# MCU.net
KiCad netlist of a schematic drawn in Altium Designer
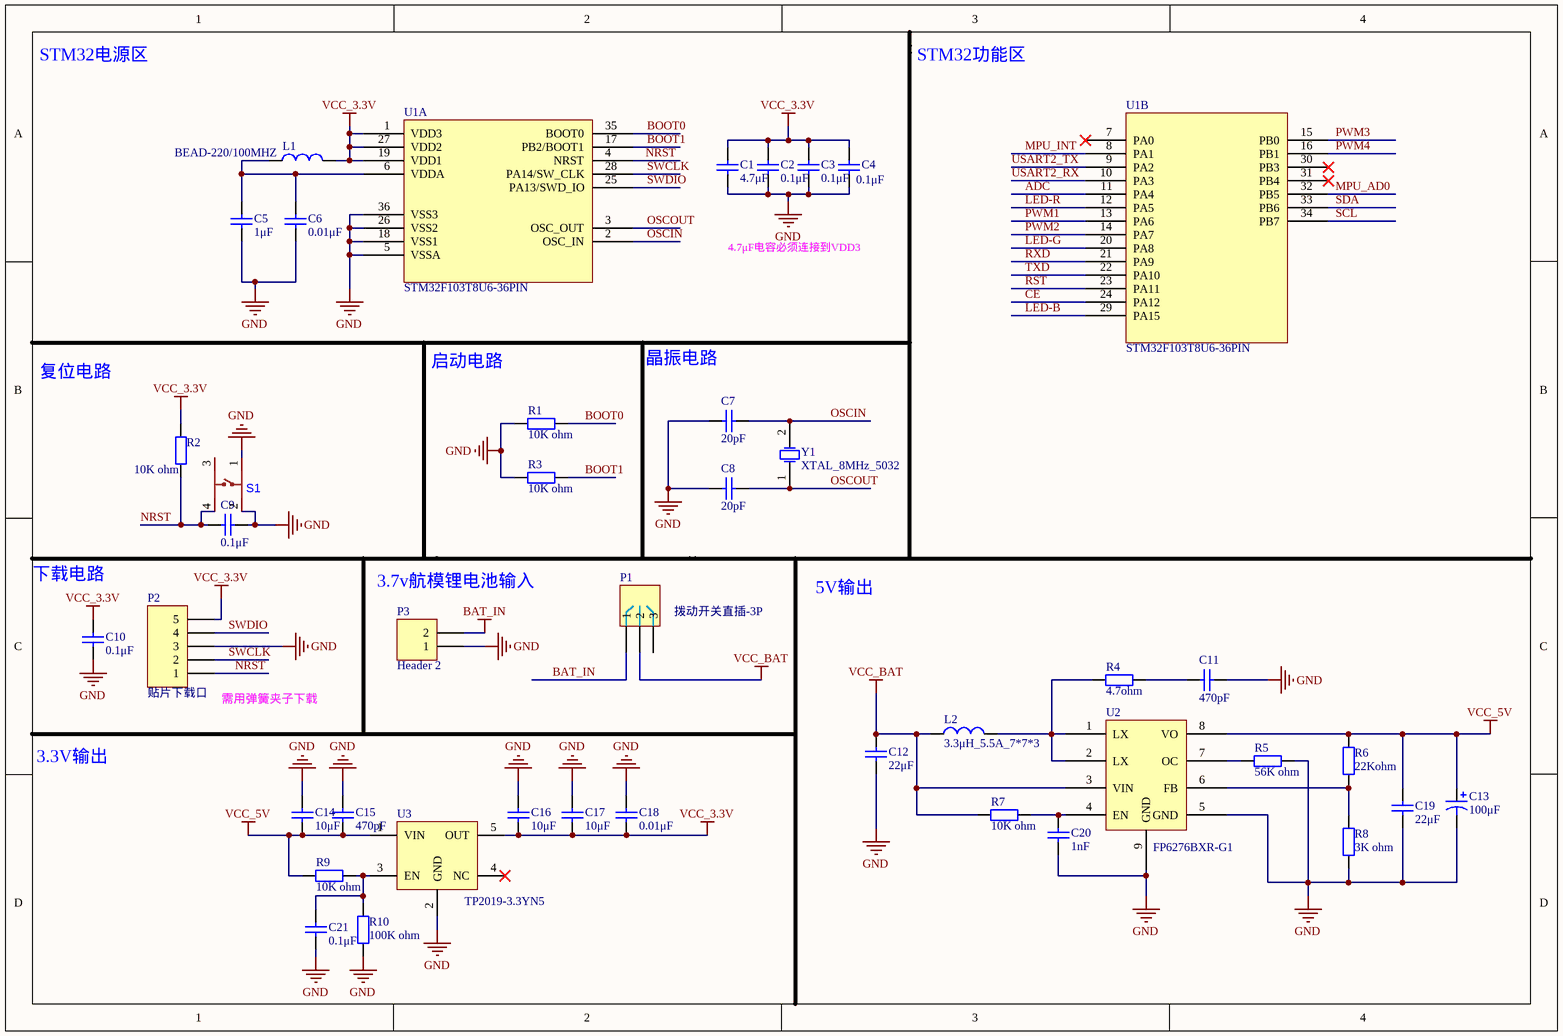
[diagram p0: MCU.SchDoc]

(export (version "E")
  (design (tool "Eeschema 10.0.6"))
  (components
    (comp (ref "C1")
      (value "4.7μF")
      (footprint "0603C")
      (description "0.1μF_50V,X7R,±5%")
      (libsource (lib "Smart-Plane_1") (part "Cap_0.1μF_50V_0603"))
    )
    (comp (ref "C2")
      (value "0.1μF")
      (footprint "0603C")
      (description "0.1μF_50V,X7R,±5%")
      (libsource (lib "Smart-Plane_1") (part "Cap_0.1μF_50V_0603"))
    )
    (comp (ref "C3")
      (value "0.1μF")
      (footprint "0603C")
      (description "0.1μF_50V,X7R,±5%")
      (libsource (lib "Smart-Plane_1") (part "Cap_0.1μF_50V_0603"))
    )
    (comp (ref "C4")
      (value "0.1μF")
      (footprint "0603C")
      (description "0.1μF_50V,X7R,±5%")
      (libsource (lib "Smart-Plane_1") (part "Cap_0.1μF_50V_0603"))
    )
    (comp (ref "C5")
      (value "1μF")
      (footprint "0603C")
      (description "0.1μF_50V,X7R,±5%")
      (libsource (lib "Smart-Plane_1") (part "Cap_0.1μF_50V_0603"))
    )
    (comp (ref "C6")
      (value "0.01μF")
      (footprint "0603C")
      (description "0.1μF_50V,X7R,±5%")
      (libsource (lib "Smart-Plane_1") (part "Cap_0.1μF_50V_0603"))
    )
    (comp (ref "C7")
      (value "20pF")
      (footprint "0603C")
      (description "20pF_50V,CH,±5%")
      (libsource (lib "Yang_Lib") (part "Cap_20pF_50V_0603"))
    )
    (comp (ref "C8")
      (value "20pF")
      (footprint "0603C")
      (description "20pF_50V,CH,±5%")
      (libsource (lib "Yang_Lib") (part "Cap_20pF_50V_0603"))
    )
    (comp (ref "C9")
      (value "0.1μF")
      (footprint "0603C")
      (description "0.1μF_50V,X7R,±5%")
      (libsource (lib "Smart-Plane_1") (part "Cap_0.1μF_50V_0603"))
    )
    (comp (ref "C10")
      (value "0.1μF")
      (footprint "0603C")
      (description "0.1μF_50V,X7R,±5%")
      (libsource (lib "Smart-Plane_1") (part "Cap_0.1μF_50V_0603"))
    )
    (comp (ref "C11")
      (value "470pF")
      (footprint "0603C")
      (description "2.2nF_50V,X7R,10%")
      (libsource (lib "Yang_Lib") (part "Cap_2.2nF_50V_0603"))
    )
    (comp (ref "C12")
      (value "22μF")
      (footprint "1206C")
      (description "22μF_35V,20%")
      (libsource (lib "Yang_Lib") (part "Cap_22μF_35V_1206"))
    )
    (comp (ref "C13")
      (value "100μF")
      (footprint "D7343C")
      (description "100μF_16V")
      (libsource (lib "Yang_Lib") (part "Cap_100μF_16V_D7343"))
    )
    (comp (ref "C14")
      (value "10μF")
      (footprint "0603C")
      (description "1μF_50V,X5R,±10%")
      (libsource (lib "Yang_Lib") (part "Cap_1μF_50V_0603"))
    )
    (comp (ref "C15")
      (value "470pF")
      (footprint "0603C")
      (description "1μF_50V,X5R,±10%")
      (libsource (lib "Yang_Lib") (part "Cap_1μF_50V_0603"))
    )
    (comp (ref "C16")
      (value "10μF")
      (footprint "0603C")
      (description "1μF_50V,X5R,±10%")
      (libsource (lib "Yang_Lib") (part "Cap_1μF_50V_0603"))
    )
    (comp (ref "C17")
      (value "10μF")
      (footprint "0603C")
      (description "10μF_35V,X5R,20%")
      (libsource (lib "Yang_Lib") (part "Cap_10μF_35V_0603"))
    )
    (comp (ref "C18")
      (value "0.01μF")
      (footprint "0603C")
      (description "0.1μF_50V,X7R,±5%")
      (libsource (lib "Smart-Plane_1") (part "Cap_0.1μF_50V_0603"))
    )
    (comp (ref "C19")
      (value "22μF")
      (footprint "1206C")
      (description "22μF_35V,20%")
      (libsource (lib "Yang_Lib") (part "Cap_22μF_35V_1206"))
    )
    (comp (ref "C20")
      (value "1nF")
      (footprint "0603C")
      (description "1μF_50V,X5R,±10%")
      (libsource (lib "Yang_Lib") (part "Cap_1μF_50V_0603"))
    )
    (comp (ref "C21")
      (value "0.1μF")
      (footprint "0603C")
      (description "1μF_50V,X5R,±10%")
      (libsource (lib "Yang_Lib") (part "Cap_1μF_50V_0603"))
    )
    (comp (ref "L1")
      (value "BEAD-220/100MHZ")
      (footprint "0603R")
      (libsource (lib "Yang_Lib") (part "BEAD-220/100MHZ_0603"))
    )
    (comp (ref "L2")
      (value "3.3μH_5.5A_7*7*3")
      (footprint "7*7*3mm - 06030")
      (description "4.7μH_5.5A_")
      (libsource (lib "Yang_Lib") (part "4.7μH_5.5A_7*7*3"))
    )
    (comp (ref "P1")
      (value "拨动开关直插-3P")
      (footprint "Switch-3P")
      (libsource (lib "Smart-Telecontrol") (part "拨动开关直插-3P"))
    )
    (comp (ref "P2")
      (value "贴片下载口")
      (footprint "download")
      (description "微型下载口")
      (libsource (lib "Smart-Plane_1") (part "微型下载口"))
    )
    (comp (ref "P3")
      (value "Header 2")
      (footprint "HDR1X2")
      (description "Header, 2-Pin")
      (fields (field (name "PUBLISHER") "Altium Limited"))
      (libsource (lib "Miscellaneous Connectors") (part "Header 2"))
    )
    (comp (ref "R1")
      (value "10K ohm")
      (footprint "0603R")
      (description "10K ohm,1%")
      (libsource (lib "") (part "Res_10K ohm_0603_1"))
    )
    (comp (ref "R2")
      (value "10K ohm")
      (footprint "0603R")
      (description "10K ohm,1%")
      (libsource (lib "Smart-Plane_1") (part "Res_10K ohm_0603"))
    )
    (comp (ref "R3")
      (value "10K ohm")
      (footprint "0603R")
      (description "10K ohm,1%")
      (libsource (lib "") (part "Res_10K ohm_0603_1"))
    )
    (comp (ref "R4")
      (value "4.7ohm")
      (footprint "0603R")
      (description "24K ohm,1%")
      (libsource (lib "Yang_Lib") (part "Res_24K ohm_0603"))
    )
    (comp (ref "R5")
      (value "56K ohm")
      (footprint "0603R")
      (description "30K ohm,1%")
      (libsource (lib "Yang_Lib") (part "Res_30K ohm_0603"))
    )
    (comp (ref "R6")
      (value "22Kohm")
      (footprint "0603R")
      (description "100K ohm_5%")
      (libsource (lib "Smart-Plane_1") (part "Res_100Kohm_0603"))
    )
    (comp (ref "R7")
      (value "10K ohm")
      (footprint "0603R")
      (description "10K ohm,1%")
      (libsource (lib "") (part "Res_10K ohm_0603_1"))
    )
    (comp (ref "R8")
      (value "3K ohm")
      (footprint "0603R")
      (description "13K ohm,1%")
      (libsource (lib "Smart-Plane_1") (part "Res_13K ohm_0603"))
    )
    (comp (ref "R9")
      (value "10K ohm")
      (footprint "0603R")
      (description "10K ohm,1%")
      (libsource (lib "") (part "Res_10K ohm_0603_1"))
    )
    (comp (ref "R10")
      (value "100K ohm")
      (footprint "0603R")
      (description "10K ohm,1%")
      (libsource (lib "") (part "Res_10K ohm_0603_2"))
    )
    (comp (ref "S1")
      (value "BX-TS-26-4416TT")
      (footprint "SW-SMD_4P-L5.2-W5.2-P3.70-LS6.5")
      (fields (field (name "MANUFACTURER") "Bossie(博锡)"))
      (libsource (lib "Smart-Plane_1") (part "BX-TS-26-4416TT"))
    )
    (comp (ref "U1")
      (value "STM32F103T8U6-36PIN")
      (footprint "QFN-36N")
      (libsource (lib "Smart-Plane_1") (part "STM32F103T8U6-36PIN"))
    )
    (comp (ref "U2")
      (value "FP6276BXR-G1")
      (footprint "SO8 - FP6277")
      (description "FP6277")
      (libsource (lib "Yang_Lib") (part "FP6277"))
    )
    (comp (ref "U3")
      (value "TP2019-3.3YN5")
      (footprint "SOT-23-5")
      (libsource (lib "Smart-Telecontrol") (part "TP2019-3.3YN5"))
    )
    (comp (ref "Y1")
      (value "XTAL_8MHz_5032")
      (footprint "5032")
      (description "XTAL_8MHz")
      (libsource (lib "Yang_Lib") (part "XTAL_8MHz_5032"))
    )
  )
  (nets
    (net (code "1") (name "/ADC") (class "Default")
      (node (ref "U1") (pin "11") (pinfunction "PA4_11") (pintype "passive"))
    )
    (net (code "2") (name "/BOOT0") (class "Default")
      (node (ref "R1") (pin "2") (pinfunction "2_2") (pintype "passive"))
      (node (ref "U1") (pin "35") (pinfunction "BOOT0_35") (pintype "passive"))
    )
    (net (code "3") (name "/BOOT1") (class "Default")
      (node (ref "R3") (pin "2") (pinfunction "2_2") (pintype "passive"))
      (node (ref "U1") (pin "17") (pinfunction "PB2/BOOT1_17") (pintype "passive"))
    )
    (net (code "4") (name "/CE") (class "Default")
      (node (ref "U1") (pin "24") (pinfunction "PA12_24") (pintype "passive"))
    )
    (net (code "5") (name "/LED-B") (class "Default")
      (node (ref "U1") (pin "29") (pinfunction "PA15_29") (pintype "passive"))
    )
    (net (code "6") (name "/LED-G") (class "Default")
      (node (ref "U1") (pin "20") (pinfunction "PA8_20") (pintype "passive"))
    )
    (net (code "7") (name "/LED-R") (class "Default")
      (node (ref "U1") (pin "12") (pinfunction "PA5_12") (pintype "passive"))
    )
    (net (code "8") (name "/MPU_AD0") (class "Default")
      (node (ref "U1") (pin "32") (pinfunction "PB5_32") (pintype "passive"))
    )
    (net (code "9") (name "/MPU_INT") (class "Default")
      (node (ref "U1") (pin "8") (pinfunction "PA1_8") (pintype "passive"))
    )
    (net (code "10") (name "/NRST") (class "Default")
      (node (ref "C9") (pin "2") (pinfunction "2_2") (pintype "passive"))
      (node (ref "P2") (pin "1") (pinfunction "1_1") (pintype "passive"))
      (node (ref "R2") (pin "2") (pinfunction "2_2") (pintype "passive"))
      (node (ref "S1") (pin "4") (pinfunction "4_4") (pintype "passive"))
      (node (ref "U1") (pin "4") (pinfunction "NRST_4") (pintype "passive"))
    )
    (net (code "11") (name "/OSCIN") (class "Default")
      (node (ref "C7") (pin "2") (pinfunction "2_2") (pintype "passive"))
      (node (ref "U1") (pin "2") (pinfunction "OSC_IN_2") (pintype "passive"))
      (node (ref "Y1") (pin "2") (pinfunction "OSC2_2") (pintype "passive"))
    )
    (net (code "12") (name "/OSCOUT") (class "Default")
      (node (ref "C8") (pin "2") (pinfunction "2_2") (pintype "passive"))
      (node (ref "U1") (pin "3") (pinfunction "OSC_OUT_3") (pintype "passive"))
      (node (ref "Y1") (pin "1") (pinfunction "OSC1_1") (pintype "passive"))
    )
    (net (code "13") (name "/PWM1") (class "Default")
      (node (ref "U1") (pin "13") (pinfunction "PA6_13") (pintype "passive"))
    )
    (net (code "14") (name "/PWM2") (class "Default")
      (node (ref "U1") (pin "14") (pinfunction "PA7_14") (pintype "passive"))
    )
    (net (code "15") (name "/PWM3") (class "Default")
      (node (ref "U1") (pin "15") (pinfunction "PB0_15") (pintype "passive"))
    )
    (net (code "16") (name "/PWM4") (class "Default")
      (node (ref "U1") (pin "16") (pinfunction "PB1_16") (pintype "passive"))
    )
    (net (code "17") (name "/RST") (class "Default")
      (node (ref "U1") (pin "23") (pinfunction "PA11_23") (pintype "passive"))
    )
    (net (code "18") (name "/RXD") (class "Default")
      (node (ref "U1") (pin "21") (pinfunction "PA9_21") (pintype "passive"))
    )
    (net (code "19") (name "/SCL") (class "Default")
      (node (ref "U1") (pin "34") (pinfunction "PB7_34") (pintype "passive"))
    )
    (net (code "20") (name "/SDA") (class "Default")
      (node (ref "U1") (pin "33") (pinfunction "PB6_33") (pintype "passive"))
    )
    (net (code "21") (name "/SWCLK") (class "Default")
      (node (ref "P2") (pin "2") (pinfunction "2_2") (pintype "passive"))
      (node (ref "U1") (pin "28") (pinfunction "PA14/SW_CLK_28") (pintype "passive"))
    )
    (net (code "22") (name "/SWDIO") (class "Default")
      (node (ref "P2") (pin "4") (pinfunction "4_4") (pintype "passive"))
      (node (ref "U1") (pin "25") (pinfunction "PA13/SWD_IO_25") (pintype "passive"))
    )
    (net (code "23") (name "/TXD") (class "Default")
      (node (ref "U1") (pin "22") (pinfunction "PA10_22") (pintype "passive"))
    )
    (net (code "24") (name "/USART2_RX") (class "Default")
      (node (ref "U1") (pin "10") (pinfunction "PA3_10") (pintype "passive"))
    )
    (net (code "25") (name "/USART2_TX") (class "Default")
      (node (ref "U1") (pin "9") (pinfunction "PA2_9") (pintype "passive"))
    )
    (net (code "26") (name "BAT_IN") (class "Default")
      (node (ref "P1") (pin "1") (pinfunction "1_1") (pintype "passive"))
      (node (ref "P3") (pin "2") (pinfunction "2_2") (pintype "passive"))
    )
    (net (code "27") (name "GND") (class "Default")
      (node (ref "C1") (pin "1") (pinfunction "1_1") (pintype "passive"))
      (node (ref "C10") (pin "1") (pinfunction "1_1") (pintype "passive"))
      (node (ref "C11") (pin "1") (pinfunction "1_1") (pintype "passive"))
      (node (ref "C12") (pin "1") (pinfunction "1_1") (pintype "passive"))
      (node (ref "C13") (pin "2") (pinfunction "2_2") (pintype "passive"))
      (node (ref "C14") (pin "1") (pinfunction "1_1") (pintype "passive"))
      (node (ref "C15") (pin "1") (pinfunction "1_1") (pintype "passive"))
      (node (ref "C16") (pin "1") (pinfunction "1_1") (pintype "passive"))
      (node (ref "C17") (pin "2") (pinfunction "2_2") (pintype "passive"))
      (node (ref "C18") (pin "2") (pinfunction "2_2") (pintype "passive"))
      (node (ref "C19") (pin "1") (pinfunction "1_1") (pintype "passive"))
      (node (ref "C2") (pin "1") (pinfunction "1_1") (pintype "passive"))
      (node (ref "C20") (pin "2") (pinfunction "2_2") (pintype "passive"))
      (node (ref "C21") (pin "2") (pinfunction "2_2") (pintype "passive"))
      (node (ref "C3") (pin "1") (pinfunction "1_1") (pintype "passive"))
      (node (ref "C4") (pin "1") (pinfunction "1_1") (pintype "passive"))
      (node (ref "C5") (pin "1") (pinfunction "1_1") (pintype "passive"))
      (node (ref "C6") (pin "1") (pinfunction "1_1") (pintype "passive"))
      (node (ref "C7") (pin "1") (pinfunction "1_1") (pintype "passive"))
      (node (ref "C8") (pin "1") (pinfunction "1_1") (pintype "passive"))
      (node (ref "C9") (pin "1") (pinfunction "1_1") (pintype "passive"))
      (node (ref "P2") (pin "3") (pinfunction "3_3") (pintype "passive"))
      (node (ref "P3") (pin "1") (pinfunction "1_1") (pintype "passive"))
      (node (ref "R1") (pin "1") (pinfunction "1_1") (pintype "passive"))
      (node (ref "R10") (pin "1") (pinfunction "1_1") (pintype "passive"))
      (node (ref "R3") (pin "1") (pinfunction "1_1") (pintype "passive"))
      (node (ref "R5") (pin "2") (pinfunction "2_2") (pintype "passive"))
      (node (ref "R8") (pin "1") (pinfunction "1_1") (pintype "passive"))
      (node (ref "S1") (pin "1") (pinfunction "1_1") (pintype "passive"))
      (node (ref "S1") (pin "2") (pinfunction "2_2") (pintype "passive"))
      (node (ref "U1") (pin "18") (pinfunction "VSS1_18") (pintype "passive"))
      (node (ref "U1") (pin "26") (pinfunction "VSS2_26") (pintype "passive"))
      (node (ref "U1") (pin "36") (pinfunction "VSS3_36") (pintype "passive"))
      (node (ref "U1") (pin "5") (pinfunction "VSSA_5") (pintype "passive"))
      (node (ref "U2") (pin "5") (pinfunction "GND_5") (pintype "passive"))
      (node (ref "U2") (pin "9") (pinfunction "GND_9") (pintype "passive"))
      (node (ref "U3") (pin "2") (pinfunction "GND_2") (pintype "passive"))
    )
    (net (code "28") (name "Net-(C11-Pad2)") (class "Default")
      (node (ref "C11") (pin "2") (pinfunction "2_2") (pintype "passive"))
      (node (ref "R4") (pin "1") (pinfunction "1_1") (pintype "passive"))
    )
    (net (code "29") (name "Net-(L2-Pad2)") (class "Default")
      (node (ref "L2") (pin "2") (pinfunction "2_2") (pintype "passive"))
      (node (ref "R4") (pin "2") (pinfunction "2_2") (pintype "passive"))
      (node (ref "U2") (pin "1") (pinfunction "LX_1") (pintype "passive"))
      (node (ref "U2") (pin "2") (pinfunction "LX_2") (pintype "passive"))
    )
    (net (code "30") (name "Net-(U1A-VDDA)") (class "Default")
      (node (ref "C5") (pin "2") (pinfunction "2_2") (pintype "passive"))
      (node (ref "C6") (pin "2") (pinfunction "2_2") (pintype "passive"))
      (node (ref "L1") (pin "1") (pinfunction "1_1") (pintype "passive"))
      (node (ref "U1") (pin "6") (pinfunction "VDDA_6") (pintype "passive"))
    )
    (net (code "31") (name "Net-(U2-EN)") (class "Default")
      (node (ref "C20") (pin "1") (pinfunction "1_1") (pintype "passive"))
      (node (ref "R7") (pin "2") (pinfunction "2_2") (pintype "passive"))
      (node (ref "U2") (pin "4") (pinfunction "EN_4") (pintype "passive"))
    )
    (net (code "32") (name "Net-(U2-FB)") (class "Default")
      (node (ref "R6") (pin "1") (pinfunction "1_1") (pintype "passive"))
      (node (ref "R8") (pin "2") (pinfunction "2_2") (pintype "passive"))
      (node (ref "U2") (pin "6") (pinfunction "FB_6") (pintype "passive"))
    )
    (net (code "33") (name "Net-(U2-OC)") (class "Default")
      (node (ref "R5") (pin "1") (pinfunction "1_1") (pintype "passive"))
      (node (ref "U2") (pin "7") (pinfunction "OC_7") (pintype "passive"))
    )
    (net (code "34") (name "Net-(U3-EN)") (class "Default")
      (node (ref "C21") (pin "1") (pinfunction "1_1") (pintype "passive"))
      (node (ref "R10") (pin "2") (pinfunction "2_2") (pintype "passive"))
      (node (ref "R9") (pin "2") (pinfunction "2_2") (pintype "passive"))
      (node (ref "U3") (pin "3") (pinfunction "EN_3") (pintype "passive"))
    )
    (net (code "35") (name "VCC_3.3V") (class "Default")
      (node (ref "C1") (pin "2") (pinfunction "2_2") (pintype "passive"))
      (node (ref "C10") (pin "2") (pinfunction "2_2") (pintype "passive"))
      (node (ref "C16") (pin "2") (pinfunction "2_2") (pintype "passive"))
      (node (ref "C17") (pin "1") (pinfunction "1_1") (pintype "passive"))
      (node (ref "C18") (pin "1") (pinfunction "1_1") (pintype "passive"))
      (node (ref "C2") (pin "2") (pinfunction "2_2") (pintype "passive"))
      (node (ref "C3") (pin "2") (pinfunction "2_2") (pintype "passive"))
      (node (ref "C4") (pin "2") (pinfunction "2_2") (pintype "passive"))
      (node (ref "L1") (pin "2") (pinfunction "2_2") (pintype "passive"))
      (node (ref "P2") (pin "5") (pinfunction "5_5") (pintype "passive"))
      (node (ref "R2") (pin "1") (pinfunction "1_1") (pintype "passive"))
      (node (ref "U1") (pin "1") (pinfunction "VDD3_1") (pintype "passive"))
      (node (ref "U1") (pin "19") (pinfunction "VDD1_19") (pintype "passive"))
      (node (ref "U1") (pin "27") (pinfunction "VDD2_27") (pintype "passive"))
      (node (ref "U3") (pin "5") (pinfunction "OUT_5") (pintype "passive"))
    )
    (net (code "36") (name "VCC_5V") (class "Default")
      (node (ref "C13") (pin "1") (pinfunction "1_1") (pintype "passive"))
      (node (ref "C14") (pin "2") (pinfunction "2_2") (pintype "passive"))
      (node (ref "C15") (pin "2") (pinfunction "2_2") (pintype "passive"))
      (node (ref "C19") (pin "2") (pinfunction "2_2") (pintype "passive"))
      (node (ref "R6") (pin "2") (pinfunction "2_2") (pintype "passive"))
      (node (ref "R9") (pin "1") (pinfunction "1_1") (pintype "passive"))
      (node (ref "U2") (pin "8") (pinfunction "VO_8") (pintype "passive"))
      (node (ref "U3") (pin "1") (pinfunction "VIN_1") (pintype "passive"))
    )
    (net (code "37") (name "VCC_BAT") (class "Default")
      (node (ref "C12") (pin "2") (pinfunction "2_2") (pintype "passive"))
      (node (ref "L2") (pin "1") (pinfunction "1_1") (pintype "passive"))
      (node (ref "P1") (pin "2") (pinfunction "2_2") (pintype "passive"))
      (node (ref "R7") (pin "1") (pinfunction "1_1") (pintype "passive"))
      (node (ref "U2") (pin "3") (pinfunction "VIN_3") (pintype "passive"))
    )
    (net (code "38") (name "unconnected-(P1-Pad3)") (class "Default")
      (node (ref "P1") (pin "3") (pinfunction "3_3") (pintype "passive"))
    )
    (net (code "39") (name "unconnected-(S1-Pad3)") (class "Default")
      (node (ref "S1") (pin "3") (pinfunction "3_3") (pintype "passive"))
    )
    (net (code "40") (name "unconnected-(U1B-PA0-Pad7)") (class "Default")
      (node (ref "U1") (pin "7") (pinfunction "PA0_7") (pintype "passive+no_connect"))
    )
    (net (code "41") (name "unconnected-(U1B-PB3-Pad30)") (class "Default")
      (node (ref "U1") (pin "30") (pinfunction "PB3_30") (pintype "passive+no_connect"))
    )
    (net (code "42") (name "unconnected-(U1B-PB4-Pad31)") (class "Default")
      (node (ref "U1") (pin "31") (pinfunction "PB4_31") (pintype "passive+no_connect"))
    )
    (net (code "43") (name "unconnected-(U3-NC-Pad4)") (class "Default")
      (node (ref "U3") (pin "4") (pinfunction "NC_4") (pintype "passive+no_connect"))
    )
  )
)
